# pt100_shc.net
KiCad netlist of a schematic drawn in Altium Designer
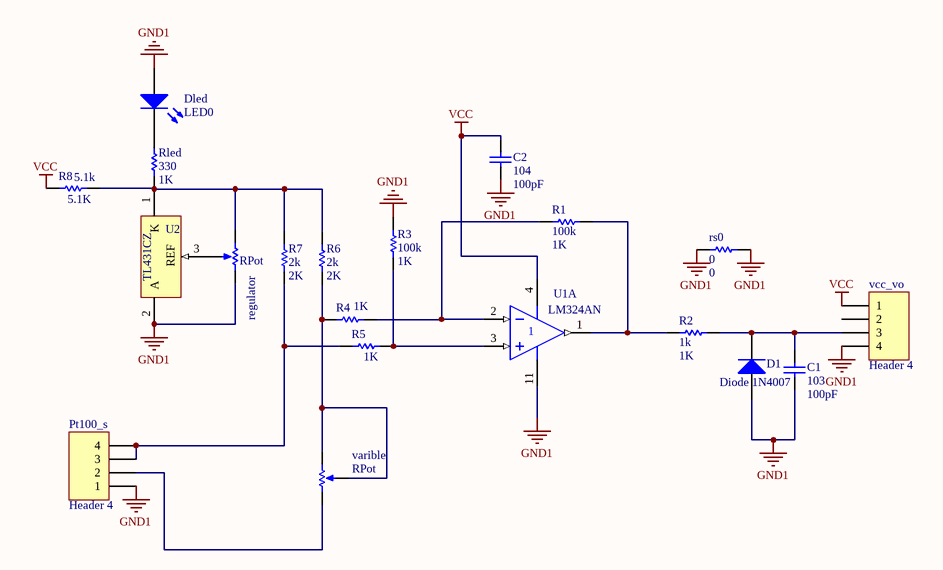
[diagram p0: pt100_shc.SchDoc]

(export (version "E")
  (design (tool "Eeschema 10.0.6"))
  (components
    (comp (ref "C1")
      (value "103")
      (footprint "RAD-0.1")
      (description "Capacitor")
      (fields (field (name "ALTIUM_VALUE") "100pF") (field (name "PUBLISHER") "Altium Limited"))
      (libsource (lib "Miscellaneous Devices") (part "Cap"))
    )
    (comp (ref "C2")
      (value "104")
      (footprint "RAD-0.1")
      (description "Capacitor")
      (fields (field (name "ALTIUM_VALUE") "100pF") (field (name "PUBLISHER") "Altium Limited"))
      (libsource (lib "Miscellaneous Devices") (part "Cap"))
    )
    (comp (ref "D1")
      (value "Diode 1N4007")
      (footprint "DIO10.46-5.3x2.8")
      (description "1 Amp General Purpose Rectifier")
      (fields (field (name "PUBLISHER") "Altium Limited"))
      (libsource (lib "Miscellaneous Devices") (part "Diode 1N4007"))
    )
    (comp (ref "Dled")
      (value "LED0")
      (footprint "CE6")
      (description "Typical INFRARED GaAs LED")
      (fields (field (name "PUBLISHER") "Altium Limited"))
      (libsource (lib "Miscellaneous Devices") (part "LED0"))
    )
    (comp (ref "Pt100_s")
      (value "Header 4")
      (footprint "HDR1X4")
      (description "Header, 4-Pin")
      (fields (field (name "PUBLISHER") "Altium Limited"))
      (libsource (lib "Miscellaneous Connectors") (part "Header 4"))
    )
    (comp (ref "R1")
      (value "100k")
      (footprint "AXIAL-0.3")
      (description "Resistor")
      (fields (field (name "ALTIUM_VALUE") "1K") (field (name "PUBLISHER") "Altium Limited"))
      (libsource (lib "Miscellaneous Devices") (part "Res1"))
    )
    (comp (ref "R2")
      (value "1k")
      (footprint "AXIAL-0.3")
      (description "Resistor")
      (fields (field (name "ALTIUM_VALUE") "1K") (field (name "PUBLISHER") "Altium Limited"))
      (libsource (lib "Miscellaneous Devices") (part "Res1"))
    )
    (comp (ref "R3")
      (value "100k")
      (footprint "AXIAL-0.3")
      (description "Resistor")
      (fields (field (name "ALTIUM_VALUE") "1K") (field (name "PUBLISHER") "Altium Limited"))
      (libsource (lib "Miscellaneous Devices") (part "Res1"))
    )
    (comp (ref "R4")
      (value "1K")
      (footprint "AXIAL-0.3")
      (description "Resistor")
      (fields (field (name "Comment") "1k") (field (name "PUBLISHER") "Altium Limited"))
      (libsource (lib "Miscellaneous Devices") (part "Res1"))
    )
    (comp (ref "R5")
      (value "1K")
      (footprint "AXIAL-0.3")
      (description "Resistor")
      (fields (field (name "Comment") "1k") (field (name "PUBLISHER") "Altium Limited"))
      (libsource (lib "Miscellaneous Devices") (part "Res1"))
    )
    (comp (ref "R6")
      (value "2k")
      (footprint "AXIAL-0.3")
      (description "Resistor")
      (fields (field (name "ALTIUM_VALUE") "2K") (field (name "PUBLISHER") "Altium Limited"))
      (libsource (lib "Miscellaneous Devices") (part "Res1"))
    )
    (comp (ref "R7")
      (value "2k")
      (footprint "AXIAL-0.3")
      (description "Resistor")
      (fields (field (name "ALTIUM_VALUE") "2K") (field (name "PUBLISHER") "Altium Limited"))
      (libsource (lib "Miscellaneous Devices") (part "Res1"))
    )
    (comp (ref "R8")
      (value "5.1k")
      (footprint "AXIAL-0.3")
      (description "Resistor")
      (fields (field (name "ALTIUM_VALUE") "5.1K") (field (name "PUBLISHER") "Altium Limited"))
      (libsource (lib "Miscellaneous Devices") (part "Res1"))
    )
    (comp (ref "regulator")
      (value "RPot")
      (footprint "VR5")
      (description "Potentiometer")
      (fields (field (name "PUBLISHER") "Altium Limited"))
      (libsource (lib "Miscellaneous Devices") (part "RPot"))
    )
    (comp (ref "Rled")
      (value "330")
      (footprint "AXIAL-0.3")
      (description "Resistor")
      (fields (field (name "ALTIUM_VALUE") "1K") (field (name "PUBLISHER") "Altium Limited"))
      (libsource (lib "Miscellaneous Devices") (part "Res1"))
    )
    (comp (ref "rs0")
      (value "0")
      (footprint "AXIAL-0.3")
      (description "Resistor")
      (fields (field (name "ALTIUM_VALUE") "0") (field (name "PUBLISHER") "Altium Limited"))
      (libsource (lib "Miscellaneous Devices") (part "Res1"))
    )
    (comp (ref "U1")
      (value "LM324AN")
      (footprint "N014")
      (description "Quadruple Operational Amplifier")
      (fields (field (name "PUBLISHER") "Altium Limited"))
      (libsource (lib "TI Operational Amplifier") (part "LM324AN"))
    )
    (comp (ref "U2")
      (value "TL431CZ")
      (footprint "TO92")
      (description "Programmable Voltage Reference")
      (fields (field (name "PUBLISHER") "Altium Limited"))
      (libsource (lib "ST Power Mgt Voltage Reference") (part "TL431CZ"))
    )
    (comp (ref "varible")
      (value "RPot")
      (footprint "VR5")
      (description "Potentiometer")
      (fields (field (name "PUBLISHER") "Altium Limited"))
      (libsource (lib "Miscellaneous Devices") (part "RPot"))
    )
    (comp (ref "vcc_vo")
      (value "Header 4")
      (footprint "HDR1X4")
      (description "Header, 4-Pin")
      (fields (field (name "PUBLISHER") "Altium Limited"))
      (libsource (lib "") (part "Header 4_1"))
    )
  )
  (nets
    (net (code "1") (name "GND1") (class "Default")
      (node (ref "C1") (pin "1") (pinfunction "1_1") (pintype "passive"))
      (node (ref "C2") (pin "1") (pinfunction "1_1") (pintype "passive"))
      (node (ref "D1") (pin "1") (pinfunction "A_1") (pintype "passive"))
      (node (ref "Dled") (pin "1") (pinfunction "A_1") (pintype "passive"))
      (node (ref "Pt100_s") (pin "1") (pinfunction "1_1") (pintype "passive"))
      (node (ref "R3") (pin "2") (pinfunction "2_2") (pintype "passive"))
      (node (ref "U1") (pin "11") (pinfunction "V-_11") (pintype "power_in"))
      (node (ref "U2") (pin "2") (pinfunction "A_2") (pintype "passive"))
      (node (ref "regulator") (pin "2") (pinfunction "BOT_2") (pintype "passive"))
      (node (ref "rs0") (pin "1") (pinfunction "1_1") (pintype "passive"))
      (node (ref "rs0") (pin "2") (pinfunction "2_2") (pintype "passive"))
      (node (ref "vcc_vo") (pin "4") (pinfunction "4_4") (pintype "passive"))
    )
    (net (code "2") (name "Net-(D1-K)") (class "Default")
      (node (ref "C1") (pin "2") (pinfunction "2_2") (pintype "passive"))
      (node (ref "D1") (pin "2") (pinfunction "K_2") (pintype "passive"))
      (node (ref "R2") (pin "2") (pinfunction "2_2") (pintype "passive"))
      (node (ref "vcc_vo") (pin "3") (pinfunction "3_3") (pintype "passive"))
    )
    (net (code "3") (name "Net-(Dled-K)") (class "Default")
      (node (ref "Dled") (pin "2") (pinfunction "K_2") (pintype "passive"))
      (node (ref "Rled") (pin "2") (pinfunction "2_2") (pintype "passive"))
    )
    (net (code "4") (name "Net-(Pt100_s-Pad3)") (class "Default")
      (node (ref "Pt100_s") (pin "3") (pinfunction "3_3") (pintype "passive"))
      (node (ref "Pt100_s") (pin "4") (pinfunction "4_4") (pintype "passive"))
      (node (ref "R5") (pin "1") (pinfunction "1_1") (pintype "passive"))
      (node (ref "R7") (pin "1") (pinfunction "1_1") (pintype "passive"))
    )
    (net (code "5") (name "Net-(U1A-IN+)") (class "Default")
      (node (ref "R3") (pin "1") (pinfunction "1_1") (pintype "passive"))
      (node (ref "R5") (pin "2") (pinfunction "2_2") (pintype "passive"))
      (node (ref "U1") (pin "3") (pinfunction "IN+_3") (pintype "input"))
    )
    (net (code "6") (name "Net-(U1A-IN-)") (class "Default")
      (node (ref "R1") (pin "1") (pinfunction "1_1") (pintype "passive"))
      (node (ref "R4") (pin "2") (pinfunction "2_2") (pintype "passive"))
      (node (ref "U1") (pin "2") (pinfunction "IN-_2") (pintype "input"))
    )
    (net (code "7") (name "Net-(U1A-OUT)") (class "Default")
      (node (ref "R1") (pin "2") (pinfunction "2_2") (pintype "passive"))
      (node (ref "R2") (pin "1") (pinfunction "1_1") (pintype "passive"))
      (node (ref "U1") (pin "1") (pinfunction "OUT_1") (pintype "output"))
    )
    (net (code "8") (name "Net-(U2-K)") (class "Default")
      (node (ref "R6") (pin "2") (pinfunction "2_2") (pintype "passive"))
      (node (ref "R7") (pin "2") (pinfunction "2_2") (pintype "passive"))
      (node (ref "R8") (pin "2") (pinfunction "2_2") (pintype "passive"))
      (node (ref "Rled") (pin "1") (pinfunction "1_1") (pintype "passive"))
      (node (ref "U2") (pin "1") (pinfunction "K_1") (pintype "passive"))
      (node (ref "regulator") (pin "1") (pinfunction "TOP_1") (pintype "passive"))
    )
    (net (code "9") (name "Net-(U2-REF)") (class "Default")
      (node (ref "U2") (pin "3") (pinfunction "REF_3") (pintype "input"))
      (node (ref "regulator") (pin "3") (pinfunction "TAP_3") (pintype "passive"))
    )
    (net (code "10") (name "Net-(varible-BOT)") (class "Default")
      (node (ref "R4") (pin "1") (pinfunction "1_1") (pintype "passive"))
      (node (ref "R6") (pin "1") (pinfunction "1_1") (pintype "passive"))
      (node (ref "varible") (pin "2") (pinfunction "BOT_2") (pintype "passive"))
      (node (ref "varible") (pin "3") (pinfunction "TAP_3") (pintype "passive"))
    )
    (net (code "11") (name "Net-(varible-TOP)") (class "Default")
      (node (ref "Pt100_s") (pin "2") (pinfunction "2_2") (pintype "passive"))
      (node (ref "varible") (pin "1") (pinfunction "TOP_1") (pintype "passive"))
    )
    (net (code "12") (name "VCC") (class "Default")
      (node (ref "C2") (pin "2") (pinfunction "2_2") (pintype "passive"))
      (node (ref "R8") (pin "1") (pinfunction "1_1") (pintype "passive"))
      (node (ref "U1") (pin "4") (pinfunction "V+_4") (pintype "power_in"))
      (node (ref "vcc_vo") (pin "1") (pinfunction "1_1") (pintype "passive"))
    )
    (net (code "13") (name "unconnected-(vcc_vo-Pad2)") (class "Default")
      (node (ref "vcc_vo") (pin "2") (pinfunction "2_2") (pintype "passive"))
    )
  )
)
